# 140715_AriloTX_REV2_1_0_433MHZ_td.net
KiCad netlist of a schematic drawn in EAGLE
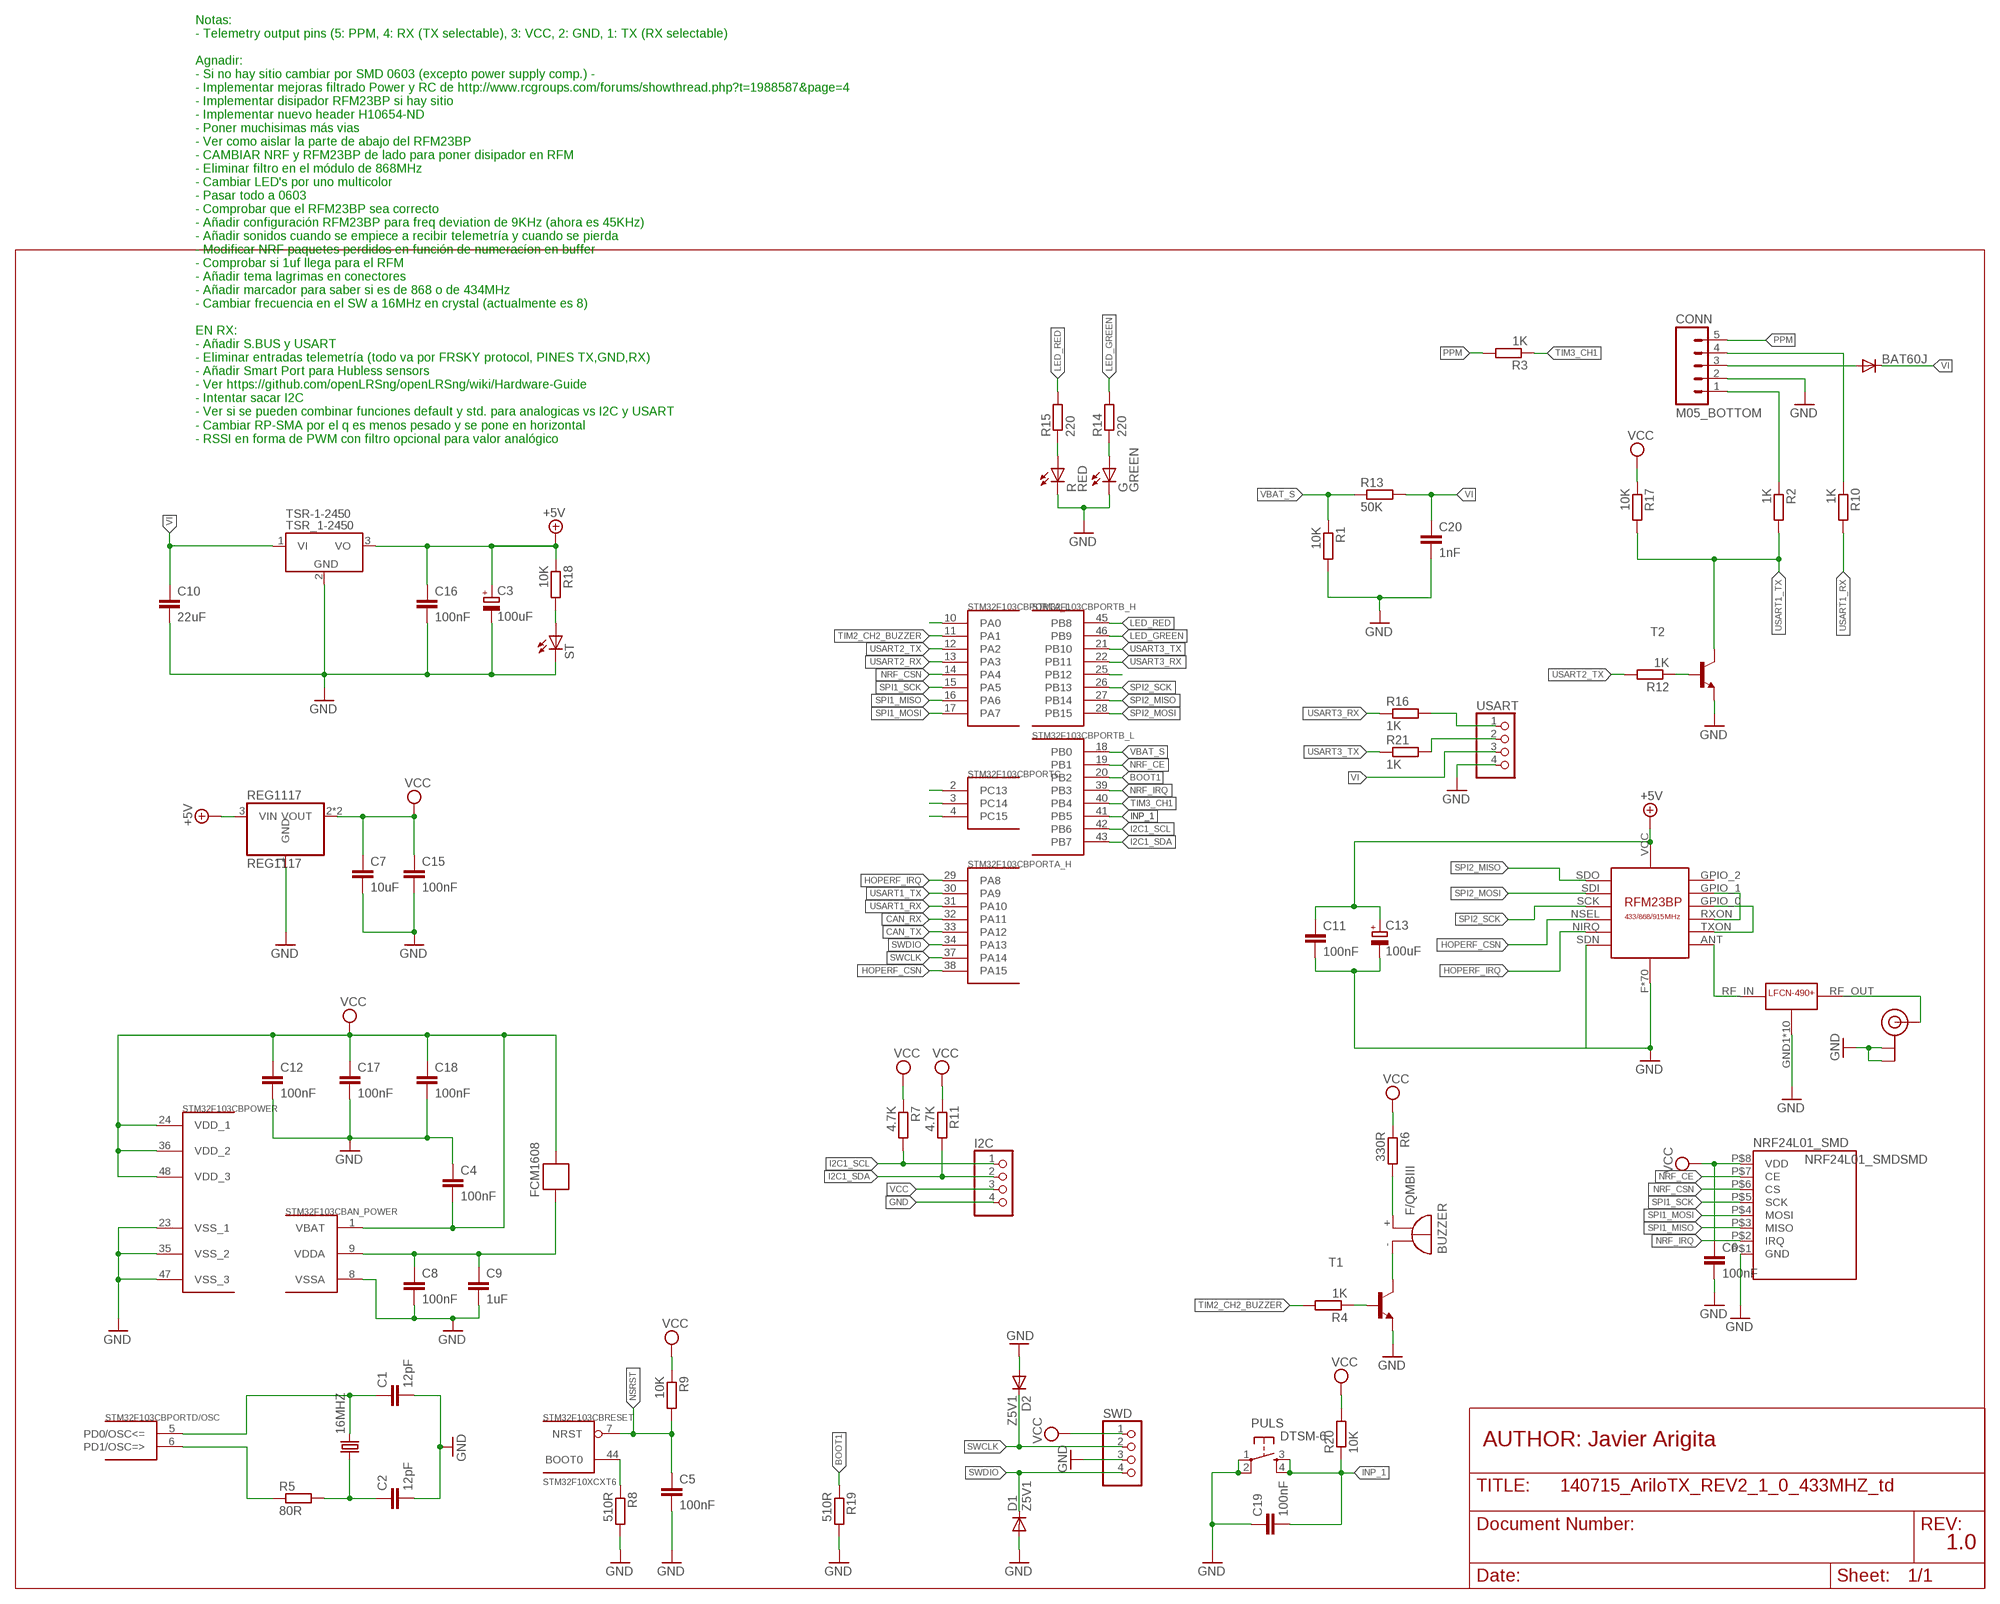
[diagram p0: schematic, sheet 1]

(export (version "E")
  (design (tool "Eeschema 10.0.6"))
  (components
    (comp (ref "16MHZ")
      (value "CRYSTAL5X3")
      (footprint "eagle-import:CRYSTAL-SMD-5X3")
      (libsource (lib "eagle-import") (part "CRYSTAL5X3"))
    )
    (comp (ref "BAT60J")
      (value "DIODE-SOD323-R")
      (footprint "eagle-import:SOD323-R")
      (libsource (lib "eagle-import") (part "DIODE-SOD323-R"))
    )
    (comp (ref "BUZZER")
      (value "F/QMBIII")
      (footprint "eagle-import:F_QMBIII")
      (libsource (lib "eagle-import") (part "F/QMBIII"))
    )
    (comp (ref "C1")
      (value "12pF")
      (footprint "eagle-import:C0603")
      (libsource (lib "eagle-import") (part "C-EUC0603"))
    )
    (comp (ref "C2")
      (value "12pF")
      (footprint "eagle-import:C0603")
      (libsource (lib "eagle-import") (part "C-EUC0603"))
    )
    (comp (ref "C3")
      (value "100uF")
      (footprint "eagle-import:SMC_B")
      (libsource (lib "eagle-import") (part "CPOL-EUSMCB"))
    )
    (comp (ref "C4")
      (value "100nF")
      (footprint "eagle-import:C0603")
      (libsource (lib "eagle-import") (part "C-EUC0603"))
    )
    (comp (ref "C5")
      (value "100nF")
      (footprint "eagle-import:C0603")
      (libsource (lib "eagle-import") (part "C-EUC0603"))
    )
    (comp (ref "C6")
      (value "100nF")
      (footprint "eagle-import:C0603")
      (libsource (lib "eagle-import") (part "C-EUC0603"))
    )
    (comp (ref "C7")
      (value "10uF")
      (footprint "eagle-import:C0805")
      (libsource (lib "eagle-import") (part "C-EUC0805"))
    )
    (comp (ref "C8")
      (value "100nF")
      (footprint "eagle-import:C0603")
      (libsource (lib "eagle-import") (part "C-EUC0603"))
    )
    (comp (ref "C9")
      (value "1uF")
      (footprint "eagle-import:C0603")
      (libsource (lib "eagle-import") (part "C-EUC0603"))
    )
    (comp (ref "C10")
      (value "22uF")
      (footprint "eagle-import:C3216")
      (libsource (lib "eagle-import") (part "resistor_C-EUC3216"))
    )
    (comp (ref "C11")
      (value "100nF")
      (footprint "eagle-import:C0603")
      (libsource (lib "eagle-import") (part "C-EUC0603"))
    )
    (comp (ref "C12")
      (value "100nF")
      (footprint "eagle-import:C0603")
      (libsource (lib "eagle-import") (part "C-EUC0603"))
    )
    (comp (ref "C13")
      (value "100uF")
      (footprint "eagle-import:SMC_B")
      (libsource (lib "eagle-import") (part "CPOL-EUSMCB"))
    )
    (comp (ref "C15")
      (value "100nF")
      (footprint "eagle-import:C0603")
      (libsource (lib "eagle-import") (part "C-EUC0603"))
    )
    (comp (ref "C16")
      (value "100nF")
      (footprint "eagle-import:C0603")
      (libsource (lib "eagle-import") (part "C-EUC0603"))
    )
    (comp (ref "C17")
      (value "100nF")
      (footprint "eagle-import:C0603")
      (libsource (lib "eagle-import") (part "C-EUC0603"))
    )
    (comp (ref "C18")
      (value "100nF")
      (footprint "eagle-import:C0603")
      (libsource (lib "eagle-import") (part "C-EUC0603"))
    )
    (comp (ref "C19")
      (value "100nF")
      (footprint "eagle-import:C0603")
      (libsource (lib "eagle-import") (part "C-EUC0603"))
    )
    (comp (ref "C20")
      (value "1nF")
      (footprint "eagle-import:C0603")
      (libsource (lib "eagle-import") (part "C-EUC0603"))
    )
    (comp (ref "CONN")
      (value "M05_BOTTOM")
      (footprint "eagle-import:M05_BOTTOM")
      (libsource (lib "eagle-import") (part "M05_BOTTOM"))
    )
    (comp (ref "D1")
      (value "Z5V1")
      (footprint "eagle-import:SOD323-R")
      (libsource (lib "eagle-import") (part "DIODE-SOD323-R"))
    )
    (comp (ref "D2")
      (value "Z5V1")
      (footprint "eagle-import:SOD323-R")
      (libsource (lib "eagle-import") (part "DIODE-SOD323-R"))
    )
    (comp (ref "FCM1608")
      (value "FERRITE-BEAD")
      (footprint "eagle-import:R0603")
      (libsource (lib "eagle-import") (part "FERRITE-BEAD"))
    )
    (comp (ref "G")
      (value "GREEN")
      (footprint "eagle-import:CHIP-LED0603")
      (libsource (lib "eagle-import") (part "LEDCHIP-LED0603"))
    )
    (comp (ref "I2C")
      (value "PINHD-1X4")
      (footprint "eagle-import:1X04")
      (libsource (lib "eagle-import") (part "PINHD-1X4"))
    )
    (comp (ref "LFCN490+")
      (value "LFCN490+")
      (footprint "eagle-import:LFCN490+")
      (libsource (lib "eagle-import") (part "LFCN490+"))
    )
    (comp (ref "NRF24L01_SMD")
      (value "NRF24L01_SMDSMD")
      (footprint "eagle-import:NRF24L01_SMD")
      (libsource (lib "eagle-import") (part "NRF24L01_SMDSMD"))
    )
    (comp (ref "PULS")
      (value "DTSM-6")
      (footprint "eagle-import:DTSM-6")
      (libsource (lib "eagle-import") (part "DTSM-6"))
    )
    (comp (ref "R")
      (value "RED")
      (footprint "eagle-import:CHIP-LED0603")
      (libsource (lib "eagle-import") (part "LEDCHIP-LED0603"))
    )
    (comp (ref "R1")
      (value "10K")
      (footprint "eagle-import:R0603")
      (libsource (lib "eagle-import") (part "R-EU_R0603"))
    )
    (comp (ref "R2")
      (value "1K")
      (footprint "eagle-import:R0603")
      (libsource (lib "eagle-import") (part "R-EU_R0603"))
    )
    (comp (ref "R3")
      (value "1K")
      (footprint "eagle-import:R0603")
      (libsource (lib "eagle-import") (part "R-EU_R0603"))
    )
    (comp (ref "R4")
      (value "1K")
      (footprint "eagle-import:R0603")
      (libsource (lib "eagle-import") (part "R-EU_R0603"))
    )
    (comp (ref "R5")
      (value "80R")
      (footprint "eagle-import:R0603")
      (libsource (lib "eagle-import") (part "R-EU_R0603"))
    )
    (comp (ref "R6")
      (value "330R")
      (footprint "eagle-import:R0603")
      (libsource (lib "eagle-import") (part "R-EU_R0603"))
    )
    (comp (ref "R7")
      (value "4.7K")
      (footprint "eagle-import:R0603")
      (libsource (lib "eagle-import") (part "R-EU_R0603"))
    )
    (comp (ref "R8")
      (value "510R")
      (footprint "eagle-import:R0603")
      (libsource (lib "eagle-import") (part "R-EU_R0603"))
    )
    (comp (ref "R9")
      (value "10K")
      (footprint "eagle-import:R0603")
      (libsource (lib "eagle-import") (part "R-EU_R0603"))
    )
    (comp (ref "R10")
      (value "1K")
      (footprint "eagle-import:R0603")
      (libsource (lib "eagle-import") (part "R-EU_R0603"))
    )
    (comp (ref "R11")
      (value "4.7K")
      (footprint "eagle-import:R0603")
      (libsource (lib "eagle-import") (part "R-EU_R0603"))
    )
    (comp (ref "R12")
      (value "1K")
      (footprint "eagle-import:R0603")
      (libsource (lib "eagle-import") (part "R-EU_R0603"))
    )
    (comp (ref "R13")
      (value "50K")
      (footprint "eagle-import:R0603")
      (libsource (lib "eagle-import") (part "R-EU_R0603"))
    )
    (comp (ref "R14")
      (value "220")
      (footprint "eagle-import:R0603")
      (libsource (lib "eagle-import") (part "R-EU_R0603"))
    )
    (comp (ref "R15")
      (value "220")
      (footprint "eagle-import:R0603")
      (libsource (lib "eagle-import") (part "R-EU_R0603"))
    )
    (comp (ref "R16")
      (value "1K")
      (footprint "eagle-import:R0603")
      (libsource (lib "eagle-import") (part "R-EU_R0603"))
    )
    (comp (ref "R17")
      (value "10K")
      (footprint "eagle-import:R0603")
      (libsource (lib "eagle-import") (part "R-EU_R0603"))
    )
    (comp (ref "R18")
      (value "10K")
      (footprint "eagle-import:R0603")
      (libsource (lib "eagle-import") (part "R-EU_R0603"))
    )
    (comp (ref "R19")
      (value "510R")
      (footprint "eagle-import:R0603")
      (libsource (lib "eagle-import") (part "R-EU_R0603"))
    )
    (comp (ref "R20")
      (value "10K")
      (footprint "eagle-import:R0603")
      (libsource (lib "eagle-import") (part "R-EU_R0603"))
    )
    (comp (ref "R21")
      (value "1K")
      (footprint "eagle-import:R0603")
      (libsource (lib "eagle-import") (part "R-EU_R0603"))
    )
    (comp (ref "REG1117")
      (value "REG1117")
      (footprint "eagle-import:SOT223")
      (libsource (lib "eagle-import") (part "REG1117"))
    )
    (comp (ref "ST")
      (value "LEDCHIP-LED0603")
      (footprint "eagle-import:CHIP-LED0603")
      (libsource (lib "eagle-import") (part "LEDCHIP-LED0603"))
    )
    (comp (ref "STM32F103CB")
      (value "STM32F10XCXT6")
      (footprint "eagle-import:TQFP48")
      (libsource (lib "eagle-import") (part "STM32F10XCXT6"))
    )
    (comp (ref "SWD")
      (value "PINHD-1X4")
      (footprint "eagle-import:1X04")
      (libsource (lib "eagle-import") (part "PINHD-1X4"))
    )
    (comp (ref "T1")
      (value "BC848-NPN-SOT23-BEC")
      (footprint "eagle-import:SOT23-BEC")
      (libsource (lib "eagle-import") (part "-NPN-SOT23-BECBC848"))
    )
    (comp (ref "T2")
      (value "BC848-NPN-SOT23-BEC")
      (footprint "eagle-import:SOT23-BEC")
      (libsource (lib "eagle-import") (part "-NPN-SOT23-BECBC848"))
    )
    (comp (ref "TSR-1-2450")
      (value "TSR_1-2450")
      (footprint "eagle-import:TSR-1")
      (libsource (lib "eagle-import") (part "TSR_1-2450"))
    )
    (comp (ref "U$1")
      (value "RFM23BP")
      (footprint "eagle-import:RFM23BP")
      (libsource (lib "eagle-import") (part "RFM23BP"))
    )
    (comp (ref "U.FL")
      (value "U.FL")
      (footprint "eagle-import:U.FL")
      (libsource (lib "eagle-import") (part "U.FL"))
    )
    (comp (ref "USART")
      (value "PINHD-1X4")
      (footprint "eagle-import:1X04")
      (libsource (lib "eagle-import") (part "PINHD-1X4"))
    )
  )
  (nets
    (net (code "1") (name "+5V") (class "Default")
      (node (ref "C11") (pin "1") (pinfunction "1_1") (pintype "passive"))
      (node (ref "C13") (pin "+") (pinfunction "+_+") (pintype "passive"))
      (node (ref "C16") (pin "1") (pinfunction "1_1") (pintype "passive"))
      (node (ref "C3") (pin "+") (pinfunction "+_+") (pintype "passive"))
      (node (ref "R18") (pin "1") (pinfunction "1_1") (pintype "passive"))
      (node (ref "REG1117") (pin "3") (pinfunction "VIN_3") (pintype "input"))
      (node (ref "TSR-1-2450") (pin "3") (pinfunction "VO_3") (pintype "power_in"))
      (node (ref "U$1") (pin "VCC") (pinfunction "VCC_VCC") (pintype "power_in"))
    )
    (net (code "2") (name "BOOT1") (class "Default")
      (node (ref "R19") (pin "1") (pinfunction "1_1") (pintype "passive"))
      (node (ref "STM32F103CB") (pin "20") (pinfunction "PB2_20") (pintype "bidirectional"))
    )
    (net (code "3") (name "CAN_RX") (class "Default")
      (node (ref "STM32F103CB") (pin "32") (pinfunction "PA11_32") (pintype "bidirectional"))
    )
    (net (code "4") (name "CAN_TX") (class "Default")
      (node (ref "STM32F103CB") (pin "33") (pinfunction "PA12_33") (pintype "bidirectional"))
    )
    (net (code "5") (name "GND") (class "Default")
      (node (ref "C1") (pin "2") (pinfunction "2_2") (pintype "passive"))
      (node (ref "C10") (pin "2") (pinfunction "2_2") (pintype "passive"))
      (node (ref "C11") (pin "2") (pinfunction "2_2") (pintype "passive"))
      (node (ref "C12") (pin "2") (pinfunction "2_2") (pintype "passive"))
      (node (ref "C13") (pin "-") (pinfunction "-_-") (pintype "passive"))
      (node (ref "C15") (pin "2") (pinfunction "2_2") (pintype "passive"))
      (node (ref "C16") (pin "2") (pinfunction "2_2") (pintype "passive"))
      (node (ref "C17") (pin "2") (pinfunction "2_2") (pintype "passive"))
      (node (ref "C18") (pin "2") (pinfunction "2_2") (pintype "passive"))
      (node (ref "C19") (pin "1") (pinfunction "1_1") (pintype "passive"))
      (node (ref "C2") (pin "2") (pinfunction "2_2") (pintype "passive"))
      (node (ref "C20") (pin "2") (pinfunction "2_2") (pintype "passive"))
      (node (ref "C3") (pin "-") (pinfunction "-_-") (pintype "passive"))
      (node (ref "C4") (pin "1") (pinfunction "1_1") (pintype "passive"))
      (node (ref "C5") (pin "2") (pinfunction "2_2") (pintype "passive"))
      (node (ref "C6") (pin "2") (pinfunction "2_2") (pintype "passive"))
      (node (ref "C7") (pin "2") (pinfunction "2_2") (pintype "passive"))
      (node (ref "C8") (pin "2") (pinfunction "2_2") (pintype "passive"))
      (node (ref "C9") (pin "2") (pinfunction "2_2") (pintype "passive"))
      (node (ref "CONN") (pin "2") (pinfunction "2_2") (pintype "passive"))
      (node (ref "D1") (pin "A") (pinfunction "A_A") (pintype "passive"))
      (node (ref "D2") (pin "A") (pinfunction "A_A") (pintype "passive"))
      (node (ref "G") (pin "C") (pinfunction "C_C") (pintype "passive"))
      (node (ref "I2C") (pin "4") (pinfunction "4_4") (pintype "passive"))
      (node (ref "LFCN490+") (pin "GND1") (pinfunction "GND_GND1") (pintype "bidirectional"))
      (node (ref "LFCN490+") (pin "GND10") (pinfunction "GND_GND10") (pintype "bidirectional"))
      (node (ref "LFCN490+") (pin "GND2") (pinfunction "GND_GND2") (pintype "bidirectional"))
      (node (ref "LFCN490+") (pin "GND3") (pinfunction "GND_GND3") (pintype "bidirectional"))
      (node (ref "LFCN490+") (pin "GND4") (pinfunction "GND_GND4") (pintype "bidirectional"))
      (node (ref "LFCN490+") (pin "GND5") (pinfunction "GND_GND5") (pintype "bidirectional"))
      (node (ref "LFCN490+") (pin "GND6") (pinfunction "GND_GND6") (pintype "bidirectional"))
      (node (ref "LFCN490+") (pin "GND7") (pinfunction "GND_GND7") (pintype "bidirectional"))
      (node (ref "LFCN490+") (pin "GND8") (pinfunction "GND_GND8") (pintype "bidirectional"))
      (node (ref "LFCN490+") (pin "GND9") (pinfunction "GND_GND9") (pintype "bidirectional"))
      (node (ref "NRF24L01_SMD") (pin "P$1") (pinfunction "GND_P$1") (pintype "power_in"))
      (node (ref "PULS") (pin "1") (pinfunction "1_1") (pintype "passive"))
      (node (ref "PULS") (pin "2") (pinfunction "2_2") (pintype "passive"))
      (node (ref "R") (pin "C") (pinfunction "C_C") (pintype "passive"))
      (node (ref "R1") (pin "2") (pinfunction "2_2") (pintype "passive"))
      (node (ref "R19") (pin "2") (pinfunction "2_2") (pintype "passive"))
      (node (ref "R8") (pin "2") (pinfunction "2_2") (pintype "passive"))
      (node (ref "REG1117") (pin "1") (pinfunction "GND_1") (pintype "power_in"))
      (node (ref "ST") (pin "C") (pinfunction "C_C") (pintype "passive"))
      (node (ref "STM32F103CB") (pin "23") (pinfunction "VSS_1_23") (pintype "power_in"))
      (node (ref "STM32F103CB") (pin "35") (pinfunction "VSS_2_35") (pintype "power_in"))
      (node (ref "STM32F103CB") (pin "47") (pinfunction "VSS_3_47") (pintype "power_in"))
      (node (ref "STM32F103CB") (pin "8") (pinfunction "VSSA_8") (pintype "power_in"))
      (node (ref "SWD") (pin "3") (pinfunction "3_3") (pintype "passive"))
      (node (ref "T1") (pin "E") (pinfunction "E_E") (pintype "passive"))
      (node (ref "T2") (pin "E") (pinfunction "E_E") (pintype "passive"))
      (node (ref "TSR-1-2450") (pin "2") (pinfunction "GND_2") (pintype "power_in"))
      (node (ref "U$1") (pin "F") (pinfunction "GND_F") (pintype "power_in"))
      (node (ref "U$1") (pin "F1") (pinfunction "GND_F1") (pintype "power_in"))
      (node (ref "U$1") (pin "F10") (pinfunction "GND_F10") (pintype "power_in"))
      (node (ref "U$1") (pin "F11") (pinfunction "GND_F11") (pintype "power_in"))
      (node (ref "U$1") (pin "F12") (pinfunction "GND_F12") (pintype "power_in"))
      (node (ref "U$1") (pin "F13") (pinfunction "GND_F13") (pintype "power_in"))
      (node (ref "U$1") (pin "F14") (pinfunction "GND_F14") (pintype "power_in"))
      (node (ref "U$1") (pin "F15") (pinfunction "GND_F15") (pintype "power_in"))
      (node (ref "U$1") (pin "F16") (pinfunction "GND_F16") (pintype "power_in"))
      (node (ref "U$1") (pin "F17") (pinfunction "GND_F17") (pintype "power_in"))
      (node (ref "U$1") (pin "F18") (pinfunction "GND_F18") (pintype "power_in"))
      (node (ref "U$1") (pin "F19") (pinfunction "GND_F19") (pintype "power_in"))
      (node (ref "U$1") (pin "F2") (pinfunction "GND_F2") (pintype "power_in"))
      (node (ref "U$1") (pin "F20") (pinfunction "GND_F20") (pintype "power_in"))
      (node (ref "U$1") (pin "F21") (pinfunction "GND_F21") (pintype "power_in"))
      (node (ref "U$1") (pin "F22") (pinfunction "GND_F22") (pintype "power_in"))
      (node (ref "U$1") (pin "F23") (pinfunction "GND_F23") (pintype "power_in"))
      (node (ref "U$1") (pin "F24") (pinfunction "GND_F24") (pintype "power_in"))
      (node (ref "U$1") (pin "F25") (pinfunction "GND_F25") (pintype "power_in"))
      (node (ref "U$1") (pin "F26") (pinfunction "GND_F26") (pintype "power_in"))
      (node (ref "U$1") (pin "F27") (pinfunction "GND_F27") (pintype "power_in"))
      (node (ref "U$1") (pin "F28") (pinfunction "GND_F28") (pintype "power_in"))
      (node (ref "U$1") (pin "F29") (pinfunction "GND_F29") (pintype "power_in"))
      (node (ref "U$1") (pin "F3") (pinfunction "GND_F3") (pintype "power_in"))
      (node (ref "U$1") (pin "F30") (pinfunction "GND_F30") (pintype "power_in"))
      (node (ref "U$1") (pin "F31") (pinfunction "GND_F31") (pintype "power_in"))
      (node (ref "U$1") (pin "F32") (pinfunction "GND_F32") (pintype "power_in"))
      (node (ref "U$1") (pin "F33") (pinfunction "GND_F33") (pintype "power_in"))
      (node (ref "U$1") (pin "F34") (pinfunction "GND_F34") (pintype "power_in"))
      (node (ref "U$1") (pin "F35") (pinfunction "GND_F35") (pintype "power_in"))
      (node (ref "U$1") (pin "F36") (pinfunction "GND_F36") (pintype "power_in"))
      (node (ref "U$1") (pin "F37") (pinfunction "GND_F37") (pintype "power_in"))
      (node (ref "U$1") (pin "F38") (pinfunction "GND_F38") (pintype "power_in"))
      (node (ref "U$1") (pin "F39") (pinfunction "GND_F39") (pintype "power_in"))
      (node (ref "U$1") (pin "F4") (pinfunction "GND_F4") (pintype "power_in"))
      (node (ref "U$1") (pin "F40") (pinfunction "GND_F40") (pintype "power_in"))
      (node (ref "U$1") (pin "F41") (pinfunction "GND_F41") (pintype "power_in"))
      (node (ref "U$1") (pin "F42") (pinfunction "GND_F42") (pintype "power_in"))
      (node (ref "U$1") (pin "F43") (pinfunction "GND_F43") (pintype "power_in"))
      (node (ref "U$1") (pin "F44") (pinfunction "GND_F44") (pintype "power_in"))
      (node (ref "U$1") (pin "F45") (pinfunction "GND_F45") (pintype "power_in"))
      (node (ref "U$1") (pin "F46") (pinfunction "GND_F46") (pintype "power_in"))
      (node (ref "U$1") (pin "F47") (pinfunction "GND_F47") (pintype "power_in"))
      (node (ref "U$1") (pin "F48") (pinfunction "GND_F48") (pintype "power_in"))
      (node (ref "U$1") (pin "F49") (pinfunction "GND_F49") (pintype "power_in"))
      (node (ref "U$1") (pin "F5") (pinfunction "GND_F5") (pintype "power_in"))
      (node (ref "U$1") (pin "F50") (pinfunction "GND_F50") (pintype "power_in"))
      (node (ref "U$1") (pin "F51") (pinfunction "GND_F51") (pintype "power_in"))
      (node (ref "U$1") (pin "F52") (pinfunction "GND_F52") (pintype "power_in"))
      (node (ref "U$1") (pin "F53") (pinfunction "GND_F53") (pintype "power_in"))
      (node (ref "U$1") (pin "F54") (pinfunction "GND_F54") (pintype "power_in"))
      (node (ref "U$1") (pin "F55") (pinfunction "GND_F55") (pintype "power_in"))
      (node (ref "U$1") (pin "F56") (pinfunction "GND_F56") (pintype "power_in"))
      (node (ref "U$1") (pin "F57") (pinfunction "GND_F57") (pintype "power_in"))
      (node (ref "U$1") (pin "F58") (pinfunction "GND_F58") (pintype "power_in"))
      (node (ref "U$1") (pin "F59") (pinfunction "GND_F59") (pintype "power_in"))
      (node (ref "U$1") (pin "F6") (pinfunction "GND_F6") (pintype "power_in"))
      (node (ref "U$1") (pin "F60") (pinfunction "GND_F60") (pintype "power_in"))
      (node (ref "U$1") (pin "F61") (pinfunction "GND_F61") (pintype "power_in"))
      (node (ref "U$1") (pin "F62") (pinfunction "GND_F62") (pintype "power_in"))
      (node (ref "U$1") (pin "F63") (pinfunction "GND_F63") (pintype "power_in"))
      (node (ref "U$1") (pin "F64") (pinfunction "GND_F64") (pintype "power_in"))
      (node (ref "U$1") (pin "F65") (pinfunction "GND_F65") (pintype "power_in"))
      (node (ref "U$1") (pin "F7") (pinfunction "GND_F7") (pintype "power_in"))
      (node (ref "U$1") (pin "F8") (pinfunction "GND_F8") (pintype "power_in"))
      (node (ref "U$1") (pin "F9") (pinfunction "GND_F9") (pintype "power_in"))
      (node (ref "U$1") (pin "GND1") (pinfunction "GND_GND1") (pintype "power_in"))
      (node (ref "U$1") (pin "GND2") (pinfunction "GND_GND2") (pintype "power_in"))
      (node (ref "U$1") (pin "GND3") (pinfunction "GND_GND3") (pintype "power_in"))
      (node (ref "U$1") (pin "GND_HEAT") (pinfunction "GND_GND_HEAT") (pintype "power_in"))
      (node (ref "U$1") (pin "SDN") (pinfunction "SDN_SDN") (pintype "bidirectional"))
      (node (ref "U.FL") (pin "P$1") (pinfunction "GND_P$1") (pintype "bidirectional"))
      (node (ref "U.FL") (pin "P$2") (pinfunction "GND_P$2") (pintype "bidirectional"))
      (node (ref "USART") (pin "4") (pinfunction "4_4") (pintype "passive"))
    )
    (net (code "6") (name "HOPERF_CSN") (class "Default")
      (node (ref "STM32F103CB") (pin "38") (pinfunction "PA15_38") (pintype "bidirectional"))
      (node (ref "U$1") (pin "NSEL") (pinfunction "NSEL_NSEL") (pintype "bidirectional"))
    )
    (net (code "7") (name "HOPERF_IRQ") (class "Default")
      (node (ref "STM32F103CB") (pin "29") (pinfunction "PA8_29") (pintype "bidirectional"))
      (node (ref "U$1") (pin "NIRQ") (pinfunction "NIRQ_NIRQ") (pintype "bidirectional"))
    )
    (net (code "8") (name "I2C1_SCL") (class "Default")
      (node (ref "I2C") (pin "1") (pinfunction "1_1") (pintype "passive"))
      (node (ref "R7") (pin "2") (pinfunction "2_2") (pintype "passive"))
      (node (ref "STM32F103CB") (pin "42") (pinfunction "PB6_42") (pintype "bidirectional"))
    )
    (net (code "9") (name "I2C1_SDA") (class "Default")
      (node (ref "I2C") (pin "2") (pinfunction "2_2") (pintype "passive"))
      (node (ref "R11") (pin "2") (pinfunction "2_2") (pintype "passive"))
      (node (ref "STM32F103CB") (pin "43") (pinfunction "PB7_43") (pintype "bidirectional"))
    )
    (net (code "10") (name "INP_1") (class "Default")
      (node (ref "C19") (pin "2") (pinfunction "2_2") (pintype "passive"))
      (node (ref "PULS") (pin "3") (pinfunction "3_3") (pintype "passive"))
      (node (ref "PULS") (pin "4") (pinfunction "4_4") (pintype "passive"))
      (node (ref "R20") (pin "1") (pinfunction "1_1") (pintype "passive"))
      (node (ref "STM32F103CB") (pin "41") (pinfunction "PB5_41") (pintype "bidirectional"))
    )
    (net (code "11") (name "LED_GREEN") (class "Default")
      (node (ref "R14") (pin "2") (pinfunction "2_2") (pintype "passive"))
      (node (ref "STM32F103CB") (pin "46") (pinfunction "PB9_46") (pintype "bidirectional"))
    )
    (net (code "12") (name "LED_RED") (class "Default")
      (node (ref "R15") (pin "2") (pinfunction "2_2") (pintype "passive"))
      (node (ref "STM32F103CB") (pin "45") (pinfunction "PB8_45") (pintype "bidirectional"))
    )
    (net (code "13") (name "NRF_CE") (class "Default")
      (node (ref "NRF24L01_SMD") (pin "P$7") (pinfunction "CE_P$7") (pintype "input"))
      (node (ref "STM32F103CB") (pin "19") (pinfunction "PB1_19") (pintype "bidirectional"))
    )
    (net (code "14") (name "NRF_CSN") (class "Default")
      (node (ref "NRF24L01_SMD") (pin "P$6") (pinfunction "CS_P$6") (pintype "input"))
      (node (ref "STM32F103CB") (pin "14") (pinfunction "PA4_14") (pintype "bidirectional"))
    )
    (net (code "15") (name "NRF_IRQ") (class "Default")
      (node (ref "NRF24L01_SMD") (pin "P$2") (pinfunction "IRQ_P$2") (pintype "output"))
      (node (ref "STM32F103CB") (pin "39") (pinfunction "PB3_39") (pintype "bidirectional"))
    )
    (net (code "16") (name "NSRST") (class "Default")
      (node (ref "C5") (pin "1") (pinfunction "1_1") (pintype "passive"))
      (node (ref "R9") (pin "2") (pinfunction "2_2") (pintype "passive"))
      (node (ref "STM32F103CB") (pin "7") (pinfunction "NRST_7") (pintype "input"))
    )
    (net (code "17") (name "Net-(16MHZ-2)") (class "Default")
      (node (ref "16MHZ") (pin "3") (pinfunction "2_3") (pintype "passive"))
      (node (ref "C1") (pin "1") (pinfunction "1_1") (pintype "passive"))
      (node (ref "STM32F103CB") (pin "5") (pinfunction "PD0/OSC<=_5") (pintype "bidirectional"))
    )
    (net (code "18") (name "Net-(16MHZ-Pad1)") (class "Default")
      (node (ref "16MHZ") (pin "1") (pinfunction "1_1") (pintype "passive"))
      (node (ref "C2") (pin "1") (pinfunction "1_1") (pintype "passive"))
      (node (ref "R5") (pin "2") (pinfunction "2_2") (pintype "passive"))
    )
    (net (code "19") (name "Net-(BAT60J-PadA)") (class "Default")
      (node (ref "BAT60J") (pin "A") (pinfunction "A_A") (pintype "passive"))
      (node (ref "CONN") (pin "3") (pinfunction "3_3") (pintype "passive"))
    )
    (net (code "20") (name "Net-(BUZZER-+)") (class "Default")
      (node (ref "BUZZER") (pin "-") (pinfunction "+_-") (pintype "passive"))
      (node (ref "T1") (pin "C") (pinfunction "C_C") (pintype "passive"))
    )
    (net (code "21") (name "Net-(BUZZER--)") (class "Default")
      (node (ref "BUZZER") (pin "+") (pinfunction "-_+") (pintype "passive"))
      (node (ref "R6") (pin "2") (pinfunction "2_2") (pintype "passive"))
    )
    (net (code "22") (name "Net-(CONN-Pad1)") (class "Default")
      (node (ref "CONN") (pin "1") (pinfunction "1_1") (pintype "passive"))
      (node (ref "R2") (pin "1") (pinfunction "1_1") (pintype "passive"))
    )
    (net (code "23") (name "Net-(CONN-Pad4)") (class "Default")
      (node (ref "CONN") (pin "4") (pinfunction "4_4") (pintype "passive"))
      (node (ref "R10") (pin "1") (pinfunction "1_1") (pintype "passive"))
    )
    (net (code "24") (name "Net-(FCM1608-P$2)") (class "Default")
      (node (ref "C8") (pin "1") (pinfunction "1_1") (pintype "passive"))
      (node (ref "C9") (pin "1") (pinfunction "1_1") (pintype "passive"))
      (node (ref "FCM1608") (pin "2") (pinfunction "P$2_2") (pintype "bidirectional"))
      (node (ref "STM32F103CB") (pin "9") (pinfunction "VDDA_9") (pintype "power_in"))
    )
    (net (code "25") (name "Net-(G-PadA)") (class "Default")
      (node (ref "G") (pin "A") (pinfunction "A_A") (pintype "passive"))
      (node (ref "R14") (pin "1") (pinfunction "1_1") (pintype "passive"))
    )
    (net (code "26") (name "Net-(LFCN490+-RF_INP)") (class "Default")
      (node (ref "LFCN490+") (pin "RF_IN") (pinfunction "RF_INP_RF_IN") (pintype "bidirectional"))
      (node (ref "U$1") (pin "ANT") (pinfunction "ANT_ANT") (pintype "bidirectional"))
    )
    (net (code "27") (name "Net-(LFCN490+-RF_OUTP)") (class "Default")
      (node (ref "LFCN490+") (pin "RF_OUT") (pinfunction "RF_OUTP_RF_OUT") (pintype "bidirectional"))
      (node (ref "U.FL") (pin "P$3") (pinfunction "SIGNAL_P$3") (pintype "bidirectional"))
    )
    (net (code "28") (name "Net-(R-PadA)") (class "Default")
      (node (ref "R") (pin "A") (pinfunction "A_A") (pintype "passive"))
      (node (ref "R15") (pin "1") (pinfunction "1_1") (pintype "passive"))
    )
    (net (code "29") (name "Net-(R4-Pad1)") (class "Default")
      (node (ref "R4") (pin "1") (pinfunction "1_1") (pintype "passive"))
      (node (ref "T1") (pin "B") (pinfunction "B_B") (pintype "passive"))
    )
    (net (code "30") (name "Net-(R12-Pad1)") (class "Default")
      (node (ref "R12") (pin "1") (pinfunction "1_1") (pintype "passive"))
      (node (ref "T2") (pin "B") (pinfunction "B_B") (pintype "passive"))
    )
    (net (code "31") (name "Net-(R16-Pad2)") (class "Default")
      (node (ref "R16") (pin "2") (pinfunction "2_2") (pintype "passive"))
      (node (ref "USART") (pin "1") (pinfunction "1_1") (pintype "passive"))
    )
    (net (code "32") (name "Net-(R18-Pad2)") (class "Default")
      (node (ref "R18") (pin "2") (pinfunction "2_2") (pintype "passive"))
      (node (ref "ST") (pin "A") (pinfunction "A_A") (pintype "passive"))
    )
    (net (code "33") (name "Net-(R21-Pad2)") (class "Default")
      (node (ref "R21") (pin "2") (pinfunction "2_2") (pintype "passive"))
      (node (ref "USART") (pin "2") (pinfunction "2_2") (pintype "passive"))
    )
    (net (code "34") (name "Net-(STM32F103CBG-PD1{slash}OSC=>)") (class "Default")
      (node (ref "R5") (pin "1") (pinfunction "1_1") (pintype "passive"))
      (node (ref "STM32F103CB") (pin "6") (pinfunction "PD1/OSC=>_6") (pintype "bidirectional"))
    )
    (net (code "35") (name "Net-(STM32F103CBI-BOOT0)") (class "Default")
      (node (ref "R8") (pin "1") (pinfunction "1_1") (pintype "passive"))
      (node (ref "STM32F103CB") (pin "44") (pinfunction "BOOT0_44") (pintype "input"))
    )
    (net (code "36") (name "Net-(U$1-PadGPIO_0)") (class "Default")
      (node (ref "U$1") (pin "GPIO_0") (pinfunction "GPIO_0_GPIO_0") (pintype "bidirectional"))
      (node (ref "U$1") (pin "TXON") (pinfunction "TXON_TXON") (pintype "bidirectional"))
    )
    (net (code "37") (name "Net-(U$1-PadGPIO_1)") (class "Default")
      (node (ref "U$1") (pin "GPIO_1") (pinfunction "GPIO_1_GPIO_1") (pintype "bidirectional"))
      (node (ref "U$1") (pin "RXON") (pinfunction "RXON_RXON") (pintype "bidirectional"))
    )
    (net (code "38") (name "PPM") (class "Default")
      (node (ref "CONN") (pin "5") (pinfunction "5_5") (pintype "passive"))
      (node (ref "R3") (pin "2") (pinfunction "2_2") (pintype "passive"))
    )
    (net (code "39") (name "SPI1_MISO") (class "Default")
      (node (ref "NRF24L01_SMD") (pin "P$3") (pinfunction "MISO_P$3") (pintype "output"))
      (node (ref "STM32F103CB") (pin "16") (pinfunction "PA6_16") (pintype "bidirectional"))
    )
    (net (code "40") (name "SPI1_MOSI") (class "Default")
      (node (ref "NRF24L01_SMD") (pin "P$4") (pinfunction "MOSI_P$4") (pintype "input"))
      (node (ref "STM32F103CB") (pin "17") (pinfunction "PA7_17") (pintype "bidirectional"))
    )
    (net (code "41") (name "SPI1_SCK") (class "Default")
      (node (ref "NRF24L01_SMD") (pin "P$5") (pinfunction "SCK_P$5") (pintype "input"))
      (node (ref "STM32F103CB") (pin "15") (pinfunction "PA5_15") (pintype "bidirectional"))
    )
    (net (code "42") (name "SPI2_MISO") (class "Default")
      (node (ref "STM32F103CB") (pin "27") (pinfunction "PB14_27") (pintype "bidirectional"))
      (node (ref "U$1") (pin "SDO") (pinfunction "SDO_SDO") (pintype "bidirectional"))
    )
    (net (code "43") (name "SPI2_MOSI") (class "Default")
      (node (ref "STM32F103CB") (pin "28") (pinfunction "PB15_28") (pintype "bidirectional"))
      (node (ref "U$1") (pin "SDI") (pinfunction "SDI_SDI") (pintype "bidirectional"))
    )
    (net (code "44") (name "SPI2_SCK") (class "Default")
      (node (ref "STM32F103CB") (pin "26") (pinfunction "PB13_26") (pintype "bidirectional"))
      (node (ref "U$1") (pin "SCK") (pinfunction "SCK_SCK") (pintype "bidirectional"))
    )
    (net (code "45") (name "SWCLK") (class "Default")
      (node (ref "D2") (pin "C") (pinfunction "C_C") (pintype "passive"))
      (node (ref "STM32F103CB") (pin "37") (pinfunction "PA14_37") (pintype "bidirectional"))
      (node (ref "SWD") (pin "2") (pinfunction "2_2") (pintype "passive"))
    )
    (net (code "46") (name "SWDIO") (class "Default")
      (node (ref "D1") (pin "C") (pinfunction "C_C") (pintype "passive"))
      (node (ref "STM32F103CB") (pin "34") (pinfunction "PA13_34") (pintype "bidirectional"))
      (node (ref "SWD") (pin "4") (pinfunction "4_4") (pintype "passive"))
    )
    (net (code "47") (name "TIM2_CH2_BUZZER") (class "Default")
      (node (ref "R4") (pin "2") (pinfunction "2_2") (pintype "passive"))
      (node (ref "STM32F103CB") (pin "11") (pinfunction "PA1_11") (pintype "bidirectional"))
    )
    (net (code "48") (name "TIM3_CH1") (class "Default")
      (node (ref "R3") (pin "1") (pinfunction "1_1") (pintype "passive"))
      (node (ref "STM32F103CB") (pin "40") (pinfunction "PB4_40") (pintype "bidirectional"))
    )
    (net (code "49") (name "USART1_RX") (class "Default")
      (node (ref "R10") (pin "2") (pinfunction "2_2") (pintype "passive"))
      (node (ref "STM32F103CB") (pin "31") (pinfunction "PA10_31") (pintype "bidirectional"))
    )
    (net (code "50") (name "USART1_TX") (class "Default")
      (node (ref "R17") (pin "2") (pinfunction "2_2") (pintype "passive"))
      (node (ref "R2") (pin "2") (pinfunction "2_2") (pintype "passive"))
      (node (ref "STM32F103CB") (pin "30") (pinfunction "PA9_30") (pintype "bidirectional"))
      (node (ref "T2") (pin "C") (pinfunction "C_C") (pintype "passive"))
    )
    (net (code "51") (name "USART2_RX") (class "Default")
      (node (ref "STM32F103CB") (pin "13") (pinfunction "PA3_13") (pintype "bidirectional"))
    )
    (net (code "52") (name "USART2_TX") (class "Default")
      (node (ref "R12") (pin "2") (pinfunction "2_2") (pintype "passive"))
      (node (ref "STM32F103CB") (pin "12") (pinfunction "PA2_12") (pintype "bidirectional"))
    )
    (net (code "53") (name "USART3_RX") (class "Default")
      (node (ref "R16") (pin "1") (pinfunction "1_1") (pintype "passive"))
      (node (ref "STM32F103CB") (pin "22") (pinfunction "PB11_22") (pintype "bidirectional"))
    )
    (net (code "54") (name "USART3_TX") (class "Default")
      (node (ref "R21") (pin "1") (pinfunction "1_1") (pintype "passive"))
      (node (ref "STM32F103CB") (pin "21") (pinfunction "PB10_21") (pintype "bidirectional"))
    )
    (net (code "55") (name "VBAT_S") (class "Default")
      (node (ref "R1") (pin "1") (pinfunction "1_1") (pintype "passive"))
      (node (ref "R13") (pin "1") (pinfunction "1_1") (pintype "passive"))
      (node (ref "STM32F103CB") (pin "18") (pinfunction "PB0_18") (pintype "bidirectional"))
    )
    (net (code "56") (name "VCC") (class "Default")
      (node (ref "C12") (pin "1") (pinfunction "1_1") (pintype "passive"))
      (node (ref "C15") (pin "1") (pinfunction "1_1") (pintype "passive"))
      (node (ref "C17") (pin "1") (pinfunction "1_1") (pintype "passive"))
      (node (ref "C18") (pin "1") (pinfunction "1_1") (pintype "passive"))
      (node (ref "C4") (pin "2") (pinfunction "2_2") (pintype "passive"))
      (node (ref "C6") (pin "1") (pinfunction "1_1") (pintype "passive"))
      (node (ref "C7") (pin "1") (pinfunction "1_1") (pintype "passive"))
      (node (ref "FCM1608") (pin "1") (pinfunction "P$1_1") (pintype "bidirectional"))
      (node (ref "I2C") (pin "3") (pinfunction "3_3") (pintype "passive"))
      (node (ref "NRF24L01_SMD") (pin "P$8") (pinfunction "VDD_P$8") (pintype "bidirectional"))
      (node (ref "R11") (pin "1") (pinfunction "1_1") (pintype "passive"))
      (node (ref "R17") (pin "1") (pinfunction "1_1") (pintype "passive"))
      (node (ref "R20") (pin "2") (pinfunction "2_2") (pintype "passive"))
      (node (ref "R6") (pin "1") (pinfunction "1_1") (pintype "passive"))
      (node (ref "R7") (pin "1") (pinfunction "1_1") (pintype "passive"))
      (node (ref "R9") (pin "1") (pinfunction "1_1") (pintype "passive"))
      (node (ref "REG1117") (pin "2") (pinfunction "VOUT_2") (pintype "power_in"))
      (node (ref "REG1117") (pin "4") (pinfunction "VOUT_4") (pintype "power_in"))
      (node (ref "STM32F103CB") (pin "1") (pinfunction "VBAT_1") (pintype "power_in"))
      (node (ref "STM32F103CB") (pin "24") (pinfunction "VDD_1_24") (pintype "power_in"))
      (node (ref "STM32F103CB") (pin "36") (pinfunction "VDD_2_36") (pintype "power_in"))
      (node (ref "STM32F103CB") (pin "48") (pinfunction "VDD_3_48") (pintype "power_in"))
      (node (ref "SWD") (pin "1") (pinfunction "1_1") (pintype "passive"))
    )
    (net (code "57") (name "VI") (class "Default")
      (node (ref "BAT60J") (pin "C") (pinfunction "C_C") (pintype "passive"))
      (node (ref "C10") (pin "1") (pinfunction "1_1") (pintype "passive"))
      (node (ref "C20") (pin "1") (pinfunction "1_1") (pintype "passive"))
      (node (ref "R13") (pin "2") (pinfunction "2_2") (pintype "passive"))
      (node (ref "TSR-1-2450") (pin "1") (pinfunction "VI_1") (pintype "power_in"))
      (node (ref "USART") (pin "3") (pinfunction "3_3") (pintype "passive"))
    )
    (net (code "58") (name "unconnected-(STM32F103CBC-PA0-Pad10)") (class "Default")
      (node (ref "STM32F103CB") (pin "10") (pinfunction "PA0_10") (pintype "bidirectional"))
    )
    (net (code "59") (name "unconnected-(STM32F103CBD-PB12-Pad25)") (class "Default")
      (node (ref "STM32F103CB") (pin "25") (pinfunction "PB12_25") (pintype "bidirectional"))
    )
    (net (code "60") (name "unconnected-(STM32F103CBF-PC13-Pad2)") (class "Default")
      (node (ref "STM32F103CB") (pin "2") (pinfunction "PC13_2") (pintype "bidirectional"))
    )
    (net (code "61") (name "unconnected-(STM32F103CBF-PC14-Pad3)") (class "Default")
      (node (ref "STM32F103CB") (pin "3") (pinfunction "PC14_3") (pintype "bidirectional"))
    )
    (net (code "62") (name "unconnected-(STM32F103CBF-PC15-Pad4)") (class "Default")
      (node (ref "STM32F103CB") (pin "4") (pinfunction "PC15_4") (pintype "bidirectional"))
    )
    (net (code "63") (name "unconnected-(U$1-PadGPIO_2)") (class "Default")
      (node (ref "U$1") (pin "GPIO_2") (pinfunction "GPIO_2_GPIO_2") (pintype "bidirectional"))
    )
  )
)
